# Wiring.net
KiCad netlist of a schematic drawn in Altium Designer
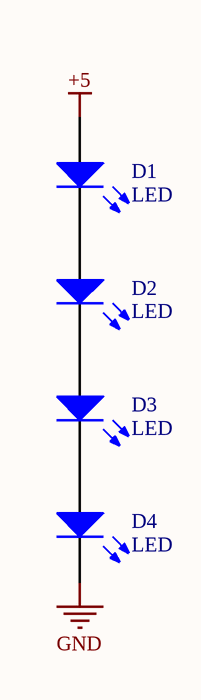
[diagram p0: Wiring.SchDoc]

(export (version "E")
  (design (tool "Eeschema 10.0.6"))
  (components
    (comp (ref "D1") (value "LED") (footprint "led") (libsource (lib "Schlib1") (part "LED3")))
    (comp (ref "D2") (value "LED") (footprint "led") (libsource (lib "Schlib1") (part "LED3")))
    (comp (ref "D3") (value "LED") (footprint "led") (libsource (lib "Schlib1") (part "LED3")))
    (comp (ref "D4") (value "LED") (footprint "led") (libsource (lib "Schlib1") (part "LED3")))
  )
  (nets
    (net (code "1") (name "+5") (class "Default")
      (node (ref "D1") (pin "1") (pinfunction "A_1") (pintype "passive"))
    )
    (net (code "2") (name "GND") (class "Default")
      (node (ref "D4") (pin "2") (pinfunction "K_2") (pintype "passive"))
    )
    (net (code "3") (name "Net-(D1-K)") (class "Default")
      (node (ref "D1") (pin "2") (pinfunction "K_2") (pintype "passive"))
      (node (ref "D2") (pin "1") (pinfunction "A_1") (pintype "passive"))
    )
    (net (code "4") (name "Net-(D2-K)") (class "Default")
      (node (ref "D2") (pin "2") (pinfunction "K_2") (pintype "passive"))
      (node (ref "D3") (pin "1") (pinfunction "A_1") (pintype "passive"))
    )
    (net (code "5") (name "Net-(D3-K)") (class "Default")
      (node (ref "D3") (pin "2") (pinfunction "K_2") (pintype "passive"))
      (node (ref "D4") (pin "1") (pinfunction "A_1") (pintype "passive"))
    )
  )
)
